# 32_ch_sample_and_hold_v3.net
KiCad netlist of a schematic drawn in EAGLE
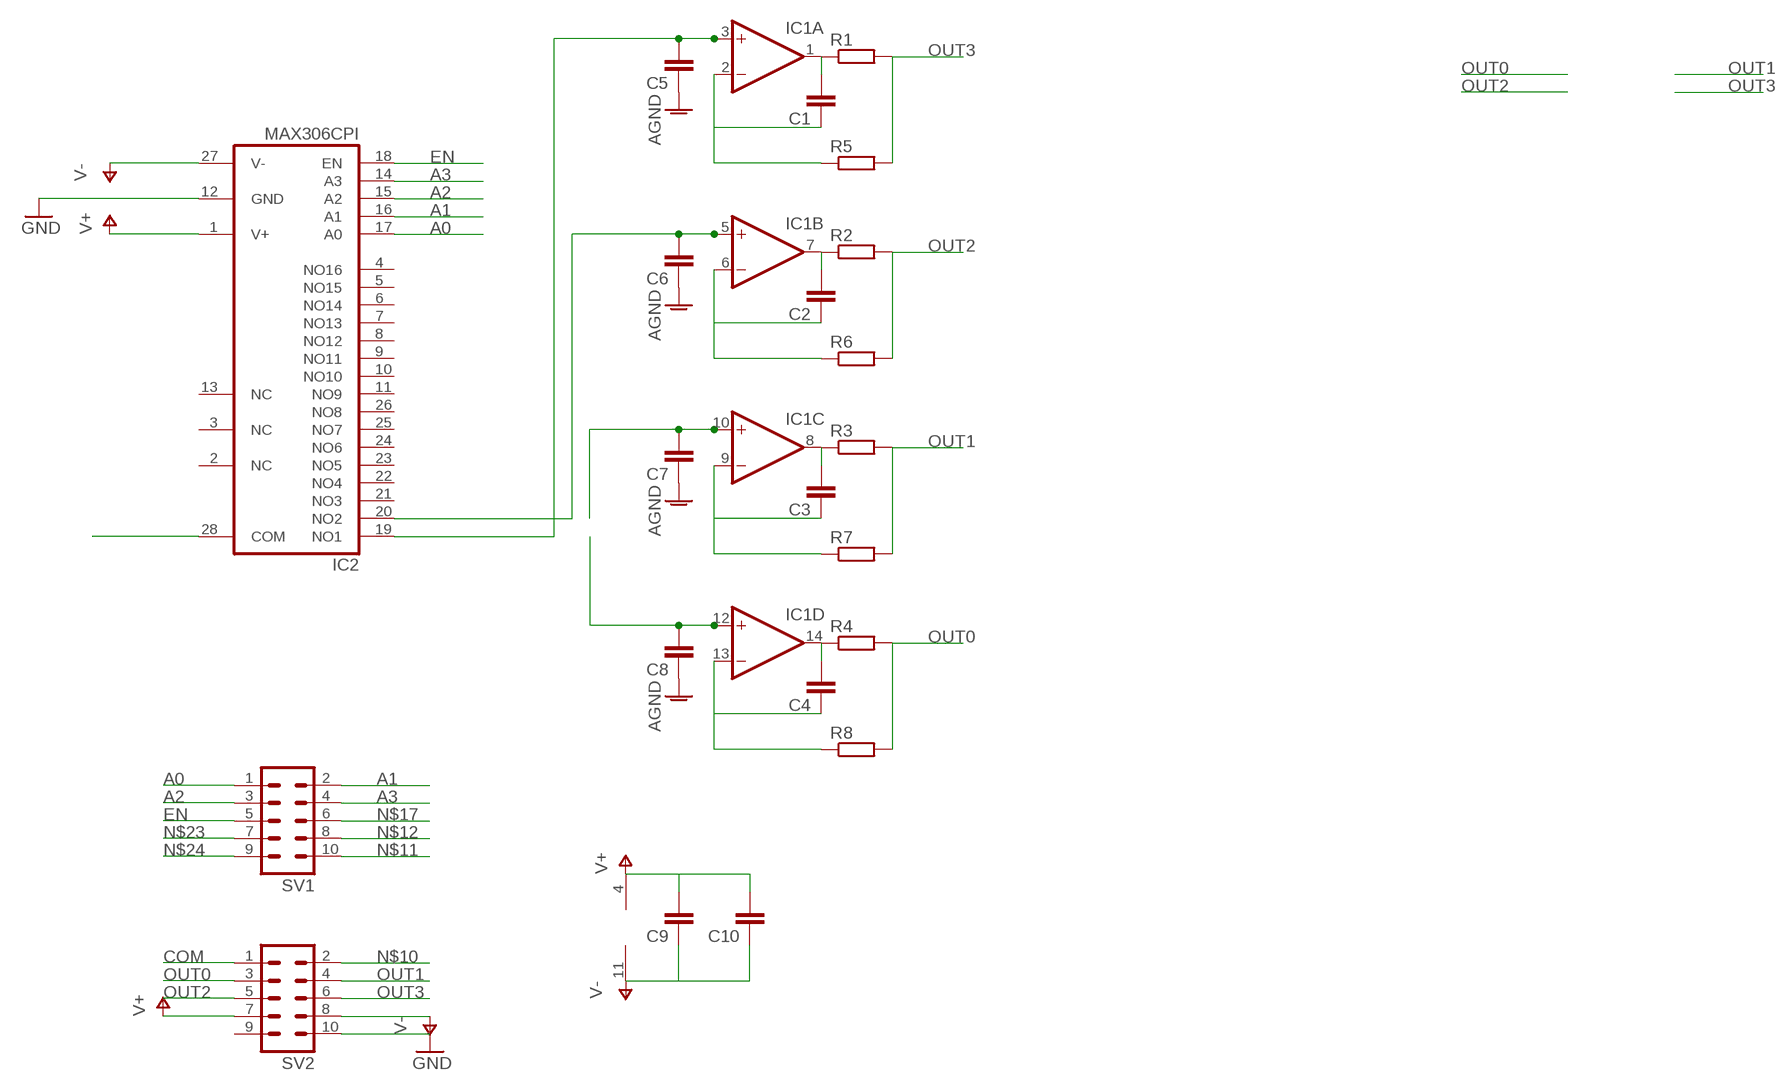
[diagram p0: schematic, sheet 1]

(export (version "E")
  (design (tool "Eeschema 10.0.6"))
  (components
    (comp (ref "C1")
      (value "C-EU025-025X050")
      (footprint "eagle-import:C025-025X050")
      (libsource (lib "eagle-import") (part "C-EU025-025X050"))
    )
    (comp (ref "C2")
      (value "C-EU025-025X050")
      (footprint "eagle-import:C025-025X050")
      (libsource (lib "eagle-import") (part "C-EU025-025X050"))
    )
    (comp (ref "C3")
      (value "C-EU025-025X050")
      (footprint "eagle-import:C025-025X050")
      (libsource (lib "eagle-import") (part "C-EU025-025X050"))
    )
    (comp (ref "C4")
      (value "C-EU025-025X050")
      (footprint "eagle-import:C025-025X050")
      (libsource (lib "eagle-import") (part "C-EU025-025X050"))
    )
    (comp (ref "C5")
      (value "C-EU025-025X050")
      (footprint "eagle-import:C025-025X050")
      (libsource (lib "eagle-import") (part "C-EU025-025X050"))
    )
    (comp (ref "C6")
      (value "C-EU025-025X050")
      (footprint "eagle-import:C025-025X050")
      (libsource (lib "eagle-import") (part "C-EU025-025X050"))
    )
    (comp (ref "C7")
      (value "C-EU025-025X050")
      (footprint "eagle-import:C025-025X050")
      (libsource (lib "eagle-import") (part "C-EU025-025X050"))
    )
    (comp (ref "C8")
      (value "C-EU025-025X050")
      (footprint "eagle-import:C025-025X050")
      (libsource (lib "eagle-import") (part "C-EU025-025X050"))
    )
    (comp (ref "C9")
      (value "C-EU025-025X050")
      (footprint "eagle-import:C025-025X050")
      (libsource (lib "eagle-import") (part "C-EU025-025X050"))
    )
    (comp (ref "C10")
      (value "C-EU025-025X050")
      (footprint "eagle-import:C025-025X050")
      (libsource (lib "eagle-import") (part "C-EU025-025X050"))
    )
    (comp (ref "IC1")
      (value "TL074P")
      (footprint "eagle-import:DIL14")
      (libsource (lib "eagle-import") (part "TL074P"))
    )
    (comp (ref "IC2")
      (value "MAX306CPI")
      (footprint "eagle-import:DIL28-6")
      (libsource (lib "eagle-import") (part "MAX306CPI"))
    )
    (comp (ref "R1")
      (value "R-EU_0207/7")
      (footprint "eagle-import:0207_7")
      (libsource (lib "eagle-import") (part "R-EU_0207/7"))
    )
    (comp (ref "R2")
      (value "R-EU_0207/7")
      (footprint "eagle-import:0207_7")
      (libsource (lib "eagle-import") (part "R-EU_0207/7"))
    )
    (comp (ref "R3")
      (value "R-EU_0207/7")
      (footprint "eagle-import:0207_7")
      (libsource (lib "eagle-import") (part "R-EU_0207/7"))
    )
    (comp (ref "R4")
      (value "R-EU_0207/7")
      (footprint "eagle-import:0207_7")
      (libsource (lib "eagle-import") (part "R-EU_0207/7"))
    )
    (comp (ref "R5")
      (value "R-EU_0207/7")
      (footprint "eagle-import:0207_7")
      (libsource (lib "eagle-import") (part "R-EU_0207/7"))
    )
    (comp (ref "R6")
      (value "R-EU_0207/7")
      (footprint "eagle-import:0207_7")
      (libsource (lib "eagle-import") (part "R-EU_0207/7"))
    )
    (comp (ref "R7")
      (value "R-EU_0207/7")
      (footprint "eagle-import:0207_7")
      (libsource (lib "eagle-import") (part "R-EU_0207/7"))
    )
    (comp (ref "R8")
      (value "R-EU_0207/7")
      (footprint "eagle-import:0207_7")
      (libsource (lib "eagle-import") (part "R-EU_0207/7"))
    )
    (comp (ref "SV1")
      (value "MA05-2")
      (footprint "eagle-import:MA05-2")
      (libsource (lib "eagle-import") (part "MA05-2"))
    )
    (comp (ref "SV2")
      (value "MA05-2")
      (footprint "eagle-import:MA05-2")
      (libsource (lib "eagle-import") (part "MA05-2"))
    )
  )
  (nets
    (net (code "1") (name "/A0") (class "Default")
      (node (ref "IC2") (pin "17") (pinfunction "A0_17") (pintype "input"))
      (node (ref "SV1") (pin "1") (pinfunction "1_1") (pintype "passive"))
    )
    (net (code "2") (name "/A1") (class "Default")
      (node (ref "IC2") (pin "16") (pinfunction "A1_16") (pintype "input"))
      (node (ref "SV1") (pin "2") (pinfunction "2_2") (pintype "passive"))
    )
    (net (code "3") (name "/A2") (class "Default")
      (node (ref "IC2") (pin "15") (pinfunction "A2_15") (pintype "input"))
      (node (ref "SV1") (pin "3") (pinfunction "3_3") (pintype "passive"))
    )
    (net (code "4") (name "/A3") (class "Default")
      (node (ref "IC2") (pin "14") (pinfunction "A3_14") (pintype "input"))
      (node (ref "SV1") (pin "4") (pinfunction "4_4") (pintype "passive"))
    )
    (net (code "5") (name "/COM") (class "Default")
      (node (ref "IC2") (pin "28") (pinfunction "COM_28") (pintype "passive"))
      (node (ref "SV2") (pin "1") (pinfunction "1_1") (pintype "passive"))
    )
    (net (code "6") (name "/EN") (class "Default")
      (node (ref "IC2") (pin "18") (pinfunction "EN_18") (pintype "input"))
      (node (ref "SV1") (pin "5") (pinfunction "5_5") (pintype "passive"))
    )
    (net (code "7") (name "/N$10") (class "Default")
      (node (ref "SV2") (pin "2") (pinfunction "2_2") (pintype "passive"))
    )
    (net (code "8") (name "/N$11") (class "Default")
      (node (ref "SV1") (pin "10") (pinfunction "10_10") (pintype "passive"))
    )
    (net (code "9") (name "/N$12") (class "Default")
      (node (ref "SV1") (pin "8") (pinfunction "8_8") (pintype "passive"))
    )
    (net (code "10") (name "/N$17") (class "Default")
      (node (ref "SV1") (pin "6") (pinfunction "6_6") (pintype "passive"))
    )
    (net (code "11") (name "/N$23") (class "Default")
      (node (ref "SV1") (pin "7") (pinfunction "7_7") (pintype "passive"))
    )
    (net (code "12") (name "/N$24") (class "Default")
      (node (ref "SV1") (pin "9") (pinfunction "9_9") (pintype "passive"))
    )
    (net (code "13") (name "/OUT0") (class "Default")
      (node (ref "R4") (pin "2") (pinfunction "2_2") (pintype "passive"))
      (node (ref "R8") (pin "2") (pinfunction "2_2") (pintype "passive"))
      (node (ref "SV2") (pin "3") (pinfunction "3_3") (pintype "passive"))
    )
    (net (code "14") (name "/OUT1") (class "Default")
      (node (ref "R3") (pin "2") (pinfunction "2_2") (pintype "passive"))
      (node (ref "R7") (pin "2") (pinfunction "2_2") (pintype "passive"))
      (node (ref "SV2") (pin "4") (pinfunction "4_4") (pintype "passive"))
    )
    (net (code "15") (name "/OUT2") (class "Default")
      (node (ref "R2") (pin "2") (pinfunction "2_2") (pintype "passive"))
      (node (ref "R6") (pin "2") (pinfunction "2_2") (pintype "passive"))
      (node (ref "SV2") (pin "5") (pinfunction "5_5") (pintype "passive"))
    )
    (net (code "16") (name "/OUT3") (class "Default")
      (node (ref "R1") (pin "2") (pinfunction "2_2") (pintype "passive"))
      (node (ref "R5") (pin "2") (pinfunction "2_2") (pintype "passive"))
      (node (ref "SV2") (pin "6") (pinfunction "6_6") (pintype "passive"))
    )
    (net (code "17") (name "AGND") (class "Default")
      (node (ref "C5") (pin "1") (pinfunction "1_1") (pintype "passive"))
      (node (ref "C6") (pin "1") (pinfunction "1_1") (pintype "passive"))
      (node (ref "C7") (pin "1") (pinfunction "1_1") (pintype "passive"))
      (node (ref "C8") (pin "1") (pinfunction "1_1") (pintype "passive"))
    )
    (net (code "18") (name "GND") (class "Default")
      (node (ref "IC2") (pin "12") (pinfunction "GND_12") (pintype "power_in"))
      (node (ref "SV2") (pin "10") (pinfunction "10_10") (pintype "passive"))
    )
    (net (code "19") (name "Net-(IC1A-+IN)") (class "Default")
      (node (ref "C5") (pin "2") (pinfunction "2_2") (pintype "passive"))
      (node (ref "IC1") (pin "3") (pinfunction "+IN_3") (pintype "input"))
      (node (ref "IC2") (pin "19") (pinfunction "NO1_19") (pintype "passive"))
    )
    (net (code "20") (name "Net-(IC1A--IN)") (class "Default")
      (node (ref "C1") (pin "1") (pinfunction "1_1") (pintype "passive"))
      (node (ref "IC1") (pin "2") (pinfunction "-IN_2") (pintype "input"))
      (node (ref "R5") (pin "1") (pinfunction "1_1") (pintype "passive"))
    )
    (net (code "21") (name "Net-(IC1A-OUT)") (class "Default")
      (node (ref "C1") (pin "2") (pinfunction "2_2") (pintype "passive"))
      (node (ref "IC1") (pin "1") (pinfunction "OUT_1") (pintype "output"))
      (node (ref "R1") (pin "1") (pinfunction "1_1") (pintype "passive"))
    )
    (net (code "22") (name "Net-(IC1B-+IN)") (class "Default")
      (node (ref "C6") (pin "2") (pinfunction "2_2") (pintype "passive"))
      (node (ref "IC1") (pin "5") (pinfunction "+IN_5") (pintype "input"))
      (node (ref "IC2") (pin "20") (pinfunction "NO2_20") (pintype "passive"))
    )
    (net (code "23") (name "Net-(IC1B--IN)") (class "Default")
      (node (ref "C2") (pin "1") (pinfunction "1_1") (pintype "passive"))
      (node (ref "IC1") (pin "6") (pinfunction "-IN_6") (pintype "input"))
      (node (ref "R6") (pin "1") (pinfunction "1_1") (pintype "passive"))
    )
    (net (code "24") (name "Net-(IC1B-OUT)") (class "Default")
      (node (ref "C2") (pin "2") (pinfunction "2_2") (pintype "passive"))
      (node (ref "IC1") (pin "7") (pinfunction "OUT_7") (pintype "output"))
      (node (ref "R2") (pin "1") (pinfunction "1_1") (pintype "passive"))
    )
    (net (code "25") (name "Net-(IC1C-+IN)") (class "Default")
      (node (ref "C7") (pin "2") (pinfunction "2_2") (pintype "passive"))
      (node (ref "IC1") (pin "10") (pinfunction "+IN_10") (pintype "input"))
    )
    (net (code "26") (name "Net-(IC1C--IN)") (class "Default")
      (node (ref "C3") (pin "1") (pinfunction "1_1") (pintype "passive"))
      (node (ref "IC1") (pin "9") (pinfunction "-IN_9") (pintype "input"))
      (node (ref "R7") (pin "1") (pinfunction "1_1") (pintype "passive"))
    )
    (net (code "27") (name "Net-(IC1C-OUT)") (class "Default")
      (node (ref "C3") (pin "2") (pinfunction "2_2") (pintype "passive"))
      (node (ref "IC1") (pin "8") (pinfunction "OUT_8") (pintype "output"))
      (node (ref "R3") (pin "1") (pinfunction "1_1") (pintype "passive"))
    )
    (net (code "28") (name "Net-(IC1D-+IN)") (class "Default")
      (node (ref "C8") (pin "2") (pinfunction "2_2") (pintype "passive"))
      (node (ref "IC1") (pin "12") (pinfunction "+IN_12") (pintype "input"))
    )
    (net (code "29") (name "Net-(IC1D--IN)") (class "Default")
      (node (ref "C4") (pin "1") (pinfunction "1_1") (pintype "passive"))
      (node (ref "IC1") (pin "13") (pinfunction "-IN_13") (pintype "input"))
      (node (ref "R8") (pin "1") (pinfunction "1_1") (pintype "passive"))
    )
    (net (code "30") (name "Net-(IC1D-OUT)") (class "Default")
      (node (ref "C4") (pin "2") (pinfunction "2_2") (pintype "passive"))
      (node (ref "IC1") (pin "14") (pinfunction "OUT_14") (pintype "output"))
      (node (ref "R4") (pin "1") (pinfunction "1_1") (pintype "passive"))
    )
    (net (code "31") (name "V+") (class "Default")
      (node (ref "C10") (pin "2") (pinfunction "2_2") (pintype "passive"))
      (node (ref "C9") (pin "2") (pinfunction "2_2") (pintype "passive"))
      (node (ref "IC1") (pin "4") (pinfunction "V+_4") (pintype "power_in"))
      (node (ref "IC2") (pin "1") (pinfunction "V+_1") (pintype "power_in"))
      (node (ref "SV2") (pin "7") (pinfunction "7_7") (pintype "passive"))
    )
    (net (code "32") (name "V-") (class "Default")
      (node (ref "C10") (pin "1") (pinfunction "1_1") (pintype "passive"))
      (node (ref "C9") (pin "1") (pinfunction "1_1") (pintype "passive"))
      (node (ref "IC1") (pin "11") (pinfunction "V-_11") (pintype "power_in"))
      (node (ref "IC2") (pin "27") (pinfunction "V-_27") (pintype "power_in"))
      (node (ref "SV2") (pin "8") (pinfunction "8_8") (pintype "passive"))
    )
    (net (code "33") (name "unconnected-(IC2-NC-Pad2)") (class "Default")
      (node (ref "IC2") (pin "2") (pinfunction "NC_2") (pintype "no_connect"))
    )
    (net (code "34") (name "unconnected-(IC2-NC-Pad3)") (class "Default")
      (node (ref "IC2") (pin "3") (pinfunction "NC_3") (pintype "no_connect"))
    )
    (net (code "35") (name "unconnected-(IC2-NC-Pad13)") (class "Default")
      (node (ref "IC2") (pin "13") (pinfunction "NC_13") (pintype "no_connect"))
    )
    (net (code "36") (name "unconnected-(IC2-NO3-Pad21)") (class "Default")
      (node (ref "IC2") (pin "21") (pinfunction "NO3_21") (pintype "passive"))
    )
    (net (code "37") (name "unconnected-(IC2-NO4-Pad22)") (class "Default")
      (node (ref "IC2") (pin "22") (pinfunction "NO4_22") (pintype "passive"))
    )
    (net (code "38") (name "unconnected-(IC2-NO5-Pad23)") (class "Default")
      (node (ref "IC2") (pin "23") (pinfunction "NO5_23") (pintype "passive"))
    )
    (net (code "39") (name "unconnected-(IC2-NO6-Pad24)") (class "Default")
      (node (ref "IC2") (pin "24") (pinfunction "NO6_24") (pintype "passive"))
    )
    (net (code "40") (name "unconnected-(IC2-NO7-Pad25)") (class "Default")
      (node (ref "IC2") (pin "25") (pinfunction "NO7_25") (pintype "passive"))
    )
    (net (code "41") (name "unconnected-(IC2-NO8-Pad26)") (class "Default")
      (node (ref "IC2") (pin "26") (pinfunction "NO8_26") (pintype "passive"))
    )
    (net (code "42") (name "unconnected-(IC2-NO9-Pad11)") (class "Default")
      (node (ref "IC2") (pin "11") (pinfunction "NO9_11") (pintype "passive"))
    )
    (net (code "43") (name "unconnected-(IC2-NO10-Pad10)") (class "Default")
      (node (ref "IC2") (pin "10") (pinfunction "NO10_10") (pintype "passive"))
    )
    (net (code "44") (name "unconnected-(IC2-NO11-Pad9)") (class "Default")
      (node (ref "IC2") (pin "9") (pinfunction "NO11_9") (pintype "passive"))
    )
    (net (code "45") (name "unconnected-(IC2-NO12-Pad8)") (class "Default")
      (node (ref "IC2") (pin "8") (pinfunction "NO12_8") (pintype "passive"))
    )
    (net (code "46") (name "unconnected-(IC2-NO13-Pad7)") (class "Default")
      (node (ref "IC2") (pin "7") (pinfunction "NO13_7") (pintype "passive"))
    )
    (net (code "47") (name "unconnected-(IC2-NO14-Pad6)") (class "Default")
      (node (ref "IC2") (pin "6") (pinfunction "NO14_6") (pintype "passive"))
    )
    (net (code "48") (name "unconnected-(IC2-NO15-Pad5)") (class "Default")
      (node (ref "IC2") (pin "5") (pinfunction "NO15_5") (pintype "passive"))
    )
    (net (code "49") (name "unconnected-(IC2-NO16-Pad4)") (class "Default")
      (node (ref "IC2") (pin "4") (pinfunction "NO16_4") (pintype "passive"))
    )
    (net (code "50") (name "unconnected-(SV2-Pad9)") (class "Default")
      (node (ref "SV2") (pin "9") (pinfunction "9_9") (pintype "passive"))
    )
  )
)
